# power_supply.net
KiCad netlist of a schematic drawn in Altium Designer
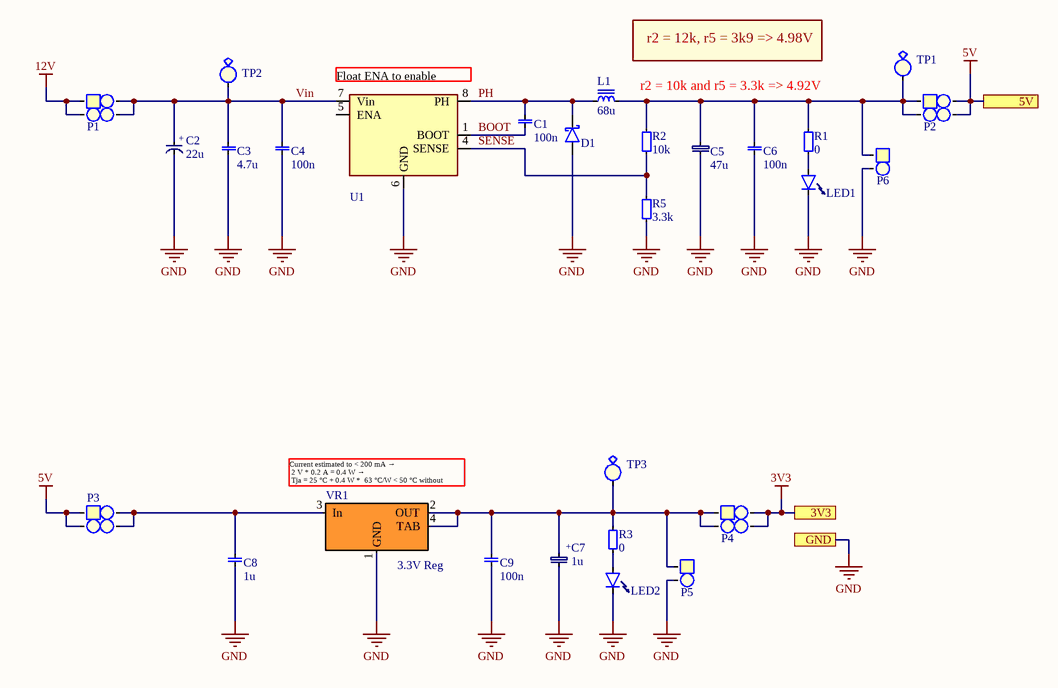
[diagram p0: power_supply.SchDoc]

(export (version "E")
  (design (tool "Eeschema 10.0.6"))
  (components
    (comp (ref "C1")
      (value "100n")
      (footprint "1210, cap")
      (fields (field (name "Comment") "1210, capacitor"))
      (libsource (lib "jclib") (part "1210, capacitor"))
    )
    (comp (ref "C2")
      (value "22u")
      (footprint "EEEFT1E220AR")
      (fields (field (name "Comment") "cap, Electrolyt Case B"))
      (libsource (lib "jclib") (part "cap, Electrolyt Case B"))
    )
    (comp (ref "C3")
      (value "4.7u")
      (footprint "1812, cap")
      (fields (field (name "PART NUMBER") "C1812C475K5RACTU") (field (name "Comment") "1812, capacitor"))
      (libsource (lib "jclib") (part "1812, capacitor"))
    )
    (comp (ref "C4")
      (value "100n")
      (footprint "1210, cap")
      (fields (field (name "Comment") "1210, capacitor"))
      (libsource (lib "jclib") (part "1210, capacitor"))
    )
    (comp (ref "C5")
      (value "47u")
      (footprint "CASE_E")
      (description "Tantalum")
      (fields (field (name "PART NUMBER") "TPSE476K020R0200") (field (name "Comment") "cap, Case E"))
      (libsource (lib "jclib") (part "cap, Case E"))
    )
    (comp (ref "C6")
      (value "100n")
      (footprint "1210, cap")
      (fields (field (name "Comment") "1210, capacitor"))
      (libsource (lib "jclib") (part "1210, capacitor"))
    )
    (comp (ref "C7")
      (value "1u")
      (footprint "CASE_B")
      (fields (field (name "Comment") "Cap, case B"))
      (libsource (lib "jclib") (part "Cap, case B"))
    )
    (comp (ref "C8")
      (value "1u")
      (footprint "0603 cap")
      (fields (field (name "Comment") "0603, capacitor"))
      (libsource (lib "jclib") (part "0603, capacitor"))
    )
    (comp (ref "C9")
      (value "100n")
      (footprint "0603 cap")
      (fields (field (name "Comment") "0603, capacitor"))
      (libsource (lib "jclib") (part "0603, capacitor"))
    )
    (comp (ref "D1")
      (value "B340A-E3/61T")
      (footprint "DO-214AC")
      (description "SchottkydiodE, 40 V, 3 A")
      (libsource (lib "jclib") (part "B340A-E3/61T"))
    )
    (comp (ref "L1")
      (value "68u")
      (footprint "MSS1260")
      (description "68 µH, 2.3 A,")
      (fields (field (name "PART NUMBER") "SRR1260-680M") (field (name "Comment") "Coil, MSS1260"))
      (libsource (lib "jclib") (part "Coil, MSS1260"))
    )
    (comp (ref "LED1")
      (value "0603, LED")
      (footprint "0603 LED")
      (libsource (lib "jclib") (part "0603, LED"))
    )
    (comp (ref "LED2")
      (value "0603, LED")
      (footprint "0603 LED")
      (libsource (lib "jclib") (part "0603, LED"))
    )
    (comp (ref "P1")
      (value "2x2 Pin Header")
      (footprint "2x2 PH")
      (libsource (lib "jclib") (part "2x2 Pin Header"))
    )
    (comp (ref "P2")
      (value "2x2 Pin Header")
      (footprint "2x2 PH")
      (libsource (lib "jclib") (part "2x2 Pin Header"))
    )
    (comp (ref "P3")
      (value "2x2 Pin Header")
      (footprint "2x2 PH")
      (libsource (lib "jclib") (part "2x2 Pin Header"))
    )
    (comp (ref "P4")
      (value "2x2 Pin Header")
      (footprint "2x2 PH")
      (libsource (lib "jclib") (part "2x2 Pin Header"))
    )
    (comp (ref "P5")
      (value "1x2 Pin Header")
      (footprint "padtwo_L")
      (description "2.54 mm, TH")
      (libsource (lib "jclib") (part "1x2 Pin Header"))
    )
    (comp (ref "P6")
      (value "1x2 Pin Header")
      (footprint "padtwo_L")
      (description "2.54 mm, TH")
      (libsource (lib "jclib") (part "1x2 Pin Header"))
    )
    (comp (ref "R1")
      (value "0")
      (footprint "0603")
      (fields (field (name "Comment") "0603, resistor"))
      (libsource (lib "jclib") (part "0603, resistor"))
    )
    (comp (ref "R2")
      (value "10k")
      (footprint "0603")
      (fields (field (name "Comment") "0603, resistor"))
      (libsource (lib "jclib") (part "0603, resistor"))
    )
    (comp (ref "R3")
      (value "0")
      (footprint "0603")
      (fields (field (name "Comment") "0603, resistor"))
      (libsource (lib "jclib") (part "0603, resistor"))
    )
    (comp (ref "R5")
      (value "3.3k")
      (footprint "0603")
      (fields (field (name "Comment") "0603, resistor"))
      (libsource (lib "jclib") (part "0603, resistor"))
    )
    (comp (ref "TP1")
      (value "Test Point")
      (footprint "testPoint")
      (libsource (lib "jclib") (part "Test Point"))
    )
    (comp (ref "TP2")
      (value "Test Point")
      (footprint "testPoint")
      (libsource (lib "jclib") (part "Test Point"))
    )
    (comp (ref "TP3")
      (value "Test Point")
      (footprint "testPoint")
      (libsource (lib "jclib") (part "Test Point"))
    )
    (comp (ref "U1")
      (value "TPS5410")
      (footprint "SOIC8")
      (description "1-A, Wide Input Range, Step-Down Converter")
      (libsource (lib "jclib") (part "TPS5410"))
    )
    (comp (ref "VR1")
      (value "3.3V Reg")
      (footprint "SOT223")
      (description "TLV1117LV 1-A, Positive Fixed-Voltage, Low-Dropout Regulator")
      (libsource (lib "jclib") (part "TLV1117LV"))
    )
  )
  (nets
    (net (code "1") (name "/BOOT") (class "Default")
      (node (ref "C1") (pin "0") (pinfunction "0_0") (pintype "passive"))
      (node (ref "U1") (pin "1") (pinfunction "BOOT_1") (pintype "passive"))
    )
    (net (code "2") (name "/PH") (class "Default")
      (node (ref "C1") (pin "1") (pinfunction "1_1") (pintype "passive"))
      (node (ref "D1") (pin "1") (pinfunction "K_1") (pintype "passive"))
      (node (ref "L1") (pin "2") (pinfunction "2_2") (pintype "passive"))
      (node (ref "U1") (pin "8") (pinfunction "PH_8") (pintype "passive"))
    )
    (net (code "3") (name "/SENSE") (class "Default")
      (node (ref "R2") (pin "1") (pinfunction "1_1") (pintype "passive"))
      (node (ref "R5") (pin "0") (pinfunction "0_0") (pintype "passive"))
      (node (ref "U1") (pin "4") (pinfunction "SENSE_4") (pintype "passive"))
    )
    (net (code "4") (name "/Vin") (class "Default")
      (node (ref "C2") (pin "2") (pinfunction "2_2") (pintype "passive"))
      (node (ref "C3") (pin "1") (pinfunction "1_1") (pintype "passive"))
      (node (ref "C4") (pin "1") (pinfunction "1_1") (pintype "passive"))
      (node (ref "P1") (pin "3") (pinfunction "3_3") (pintype "passive"))
      (node (ref "P1") (pin "4") (pinfunction "4_4") (pintype "passive"))
      (node (ref "TP2") (pin "0") (pinfunction "0_0") (pintype "passive"))
      (node (ref "U1") (pin "7") (pinfunction "Vin_7") (pintype "passive"))
    )
    (net (code "5") (name "3V3") (class "Default")
      (node (ref "P4") (pin "3") (pinfunction "3_3") (pintype "passive"))
      (node (ref "P4") (pin "4") (pinfunction "4_4") (pintype "passive"))
    )
    (net (code "6") (name "5V") (class "Default")
      (node (ref "P2") (pin "3") (pinfunction "3_3") (pintype "passive"))
      (node (ref "P2") (pin "4") (pinfunction "4_4") (pintype "passive"))
      (node (ref "P3") (pin "1") (pinfunction "1_1") (pintype "passive"))
      (node (ref "P3") (pin "2") (pinfunction "2_2") (pintype "passive"))
    )
    (net (code "7") (name "12V") (class "Default")
      (node (ref "P1") (pin "1") (pinfunction "1_1") (pintype "passive"))
      (node (ref "P1") (pin "2") (pinfunction "2_2") (pintype "passive"))
    )
    (net (code "8") (name "GND") (class "Default")
      (node (ref "C2") (pin "1") (pinfunction "1_1") (pintype "passive"))
      (node (ref "C3") (pin "0") (pinfunction "0_0") (pintype "passive"))
      (node (ref "C4") (pin "0") (pinfunction "0_0") (pintype "passive"))
      (node (ref "C5") (pin "2") (pinfunction "2_2") (pintype "passive"))
      (node (ref "C6") (pin "0") (pinfunction "0_0") (pintype "passive"))
      (node (ref "C7") (pin "1") (pinfunction "1_1") (pintype "passive"))
      (node (ref "C8") (pin "0") (pinfunction "0_0") (pintype "passive"))
      (node (ref "C9") (pin "0") (pinfunction "0_0") (pintype "passive"))
      (node (ref "D1") (pin "3") (pinfunction "A_3") (pintype "passive"))
      (node (ref "LED1") (pin "0") (pinfunction "Cathode_0") (pintype "passive"))
      (node (ref "LED2") (pin "0") (pinfunction "Cathode_0") (pintype "passive"))
      (node (ref "P5") (pin "2") (pinfunction "2_2") (pintype "passive"))
      (node (ref "P6") (pin "2") (pinfunction "2_2") (pintype "passive"))
      (node (ref "R5") (pin "1") (pinfunction "1_1") (pintype "passive"))
      (node (ref "U1") (pin "6") (pinfunction "GND_6") (pintype "passive"))
      (node (ref "VR1") (pin "1") (pinfunction "GND_1") (pintype "passive"))
    )
    (net (code "9") (name "Net-(C5-Pad1)") (class "Default")
      (node (ref "C5") (pin "1") (pinfunction "1_1") (pintype "passive"))
      (node (ref "C6") (pin "1") (pinfunction "1_1") (pintype "passive"))
      (node (ref "L1") (pin "1") (pinfunction "1_1") (pintype "passive"))
      (node (ref "P2") (pin "1") (pinfunction "1_1") (pintype "passive"))
      (node (ref "P2") (pin "2") (pinfunction "2_2") (pintype "passive"))
      (node (ref "P6") (pin "1") (pinfunction "1_1") (pintype "passive"))
      (node (ref "R1") (pin "0") (pinfunction "0_0") (pintype "passive"))
      (node (ref "R2") (pin "0") (pinfunction "0_0") (pintype "passive"))
      (node (ref "TP1") (pin "0") (pinfunction "0_0") (pintype "passive"))
    )
    (net (code "10") (name "Net-(LED1-Pad1)") (class "Default")
      (node (ref "LED1") (pin "1") (pinfunction "1_1") (pintype "passive"))
      (node (ref "R1") (pin "1") (pinfunction "1_1") (pintype "passive"))
    )
    (net (code "11") (name "Net-(LED2-Pad1)") (class "Default")
      (node (ref "LED2") (pin "1") (pinfunction "1_1") (pintype "passive"))
      (node (ref "R3") (pin "1") (pinfunction "1_1") (pintype "passive"))
    )
    (net (code "12") (name "Net-(VR1-In)") (class "Default")
      (node (ref "C8") (pin "1") (pinfunction "1_1") (pintype "passive"))
      (node (ref "P3") (pin "3") (pinfunction "3_3") (pintype "passive"))
      (node (ref "P3") (pin "4") (pinfunction "4_4") (pintype "passive"))
      (node (ref "VR1") (pin "3") (pinfunction "In_3") (pintype "passive"))
    )
    (net (code "13") (name "Net-(VR1-OUT)") (class "Default")
      (node (ref "C7") (pin "2") (pinfunction "2_2") (pintype "passive"))
      (node (ref "C9") (pin "1") (pinfunction "1_1") (pintype "passive"))
      (node (ref "P4") (pin "1") (pinfunction "1_1") (pintype "passive"))
      (node (ref "P4") (pin "2") (pinfunction "2_2") (pintype "passive"))
      (node (ref "P5") (pin "1") (pinfunction "1_1") (pintype "passive"))
      (node (ref "R3") (pin "0") (pinfunction "0_0") (pintype "passive"))
      (node (ref "TP3") (pin "0") (pinfunction "0_0") (pintype "passive"))
      (node (ref "VR1") (pin "2") (pinfunction "OUT_2") (pintype "passive"))
      (node (ref "VR1") (pin "4") (pinfunction "TAB_4") (pintype "passive"))
    )
    (net (code "14") (name "unconnected-(U1-ENA-Pad5)") (class "Default")
      (node (ref "U1") (pin "5") (pinfunction "ENA_5") (pintype "passive"))
    )
  )
)
